# CONNECTORs.net
KiCad netlist of a schematic drawn in Altium Designer
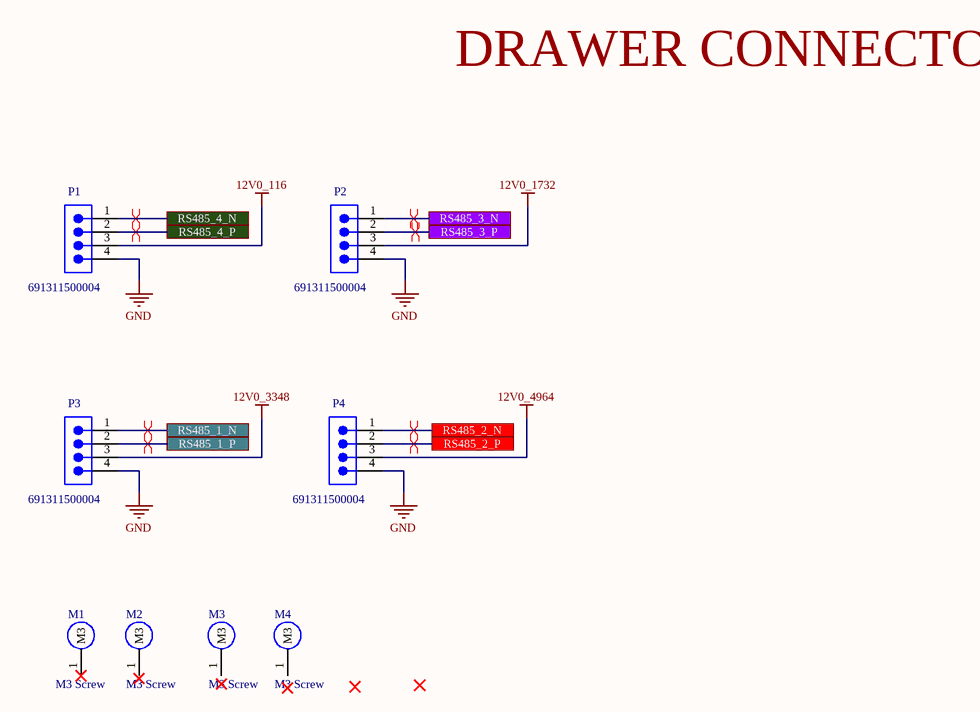
[diagram p0: CONNECTORs.SchDoc]

(export (version "E")
  (design (tool "Eeschema 10.0.6"))
  (components
    (comp (ref "M1")
      (value "M3 Screw")
      (footprint "M3_Screw")
      (description "M3 Screw Hole")
      (libsource (lib "MareLux24Lib") (part "M3 Screw"))
    )
    (comp (ref "M2")
      (value "M3 Screw")
      (footprint "M3_Screw")
      (description "M3 Screw Hole")
      (libsource (lib "MareLux24Lib") (part "M3 Screw"))
    )
    (comp (ref "M3")
      (value "M3 Screw")
      (footprint "M3_Screw")
      (description "M3 Screw Hole")
      (libsource (lib "MareLux24Lib") (part "M3 Screw"))
    )
    (comp (ref "M4")
      (value "M3 Screw")
      (footprint "M3_Screw")
      (description "M3 Screw Hole")
      (libsource (lib "MareLux24Lib") (part "M3 Screw"))
    )
    (comp (ref "P1")
      (value "691311500004")
      (footprint "691311500004")
      (description "WR-TBL Series 311 Open Vertical PCB Header, THT, pitch 5.08mm, 04p")
      (fields
        (field (name "MANUFACTURER PART NUMBER") "SBDK 5,08-E2A/4")
        (field (name "MANUFACTURER") "Wurth Elektronik")
      )
      (libsource (lib "Altium_WR-TBL_Pluggable Connector (rev25b)") (part "691311500004"))
    )
    (comp (ref "P2")
      (value "691311500004")
      (footprint "691311500004")
      (description "WR-TBL Series 311 Open Vertical PCB Header, THT, pitch 5.08mm, 04p")
      (fields
        (field (name "MANUFACTURER PART NUMBER") "SBDK 5,08-E2A/4")
        (field (name "MANUFACTURER") "Wurth Elektronik")
      )
      (libsource (lib "Altium_WR-TBL_Pluggable Connector (rev25b)") (part "691311500004"))
    )
    (comp (ref "P3")
      (value "691311500004")
      (footprint "691311500004")
      (description "WR-TBL Series 311 Open Vertical PCB Header, THT, pitch 5.08mm, 04p")
      (fields
        (field (name "MANUFACTURER PART NUMBER") "SBDK 5,08-E2A/4")
        (field (name "MANUFACTURER") "Wurth Elektronik")
      )
      (libsource (lib "Altium_WR-TBL_Pluggable Connector (rev25b)") (part "691311500004"))
    )
    (comp (ref "P4")
      (value "691311500004")
      (footprint "691311500004")
      (description "WR-TBL Series 311 Open Vertical PCB Header, THT, pitch 5.08mm, 04p")
      (fields
        (field (name "MANUFACTURER PART NUMBER") "SBDK 5,08-E2A/4")
        (field (name "MANUFACTURER") "Wurth Elektronik")
      )
      (libsource (lib "Altium_WR-TBL_Pluggable Connector (rev25b)") (part "691311500004"))
    )
  )
  (nets
    (net (code "1") (name "/RS485_1_N") (class "Default")
      (node (ref "P3") (pin "1") (pinfunction "1_1") (pintype "passive"))
    )
    (net (code "2") (name "/RS485_1_P") (class "Default")
      (node (ref "P3") (pin "2") (pinfunction "2_2") (pintype "passive"))
    )
    (net (code "3") (name "/RS485_2_N") (class "Default")
      (node (ref "P4") (pin "1") (pinfunction "1_1") (pintype "passive"))
    )
    (net (code "4") (name "/RS485_2_P") (class "Default")
      (node (ref "P4") (pin "2") (pinfunction "2_2") (pintype "passive"))
    )
    (net (code "5") (name "/RS485_3_N") (class "Default")
      (node (ref "P2") (pin "1") (pinfunction "1_1") (pintype "passive"))
    )
    (net (code "6") (name "/RS485_3_P") (class "Default")
      (node (ref "P2") (pin "2") (pinfunction "2_2") (pintype "passive"))
    )
    (net (code "7") (name "/RS485_4_N") (class "Default")
      (node (ref "P1") (pin "1") (pinfunction "1_1") (pintype "passive"))
    )
    (net (code "8") (name "/RS485_4_P") (class "Default")
      (node (ref "P1") (pin "2") (pinfunction "2_2") (pintype "passive"))
    )
    (net (code "9") (name "12V0_116") (class "Default")
      (node (ref "P1") (pin "3") (pinfunction "3_3") (pintype "passive"))
    )
    (net (code "10") (name "12V0_1732") (class "Default")
      (node (ref "P2") (pin "3") (pinfunction "3_3") (pintype "passive"))
    )
    (net (code "11") (name "12V0_3348") (class "Default")
      (node (ref "P3") (pin "3") (pinfunction "3_3") (pintype "passive"))
    )
    (net (code "12") (name "12V0_4964") (class "Default")
      (node (ref "P4") (pin "3") (pinfunction "3_3") (pintype "passive"))
    )
    (net (code "13") (name "GND") (class "Default")
      (node (ref "P1") (pin "4") (pinfunction "4_4") (pintype "passive"))
      (node (ref "P2") (pin "4") (pinfunction "4_4") (pintype "passive"))
      (node (ref "P3") (pin "4") (pinfunction "4_4") (pintype "passive"))
      (node (ref "P4") (pin "4") (pinfunction "4_4") (pintype "passive"))
    )
    (net (code "14") (name "unconnected-(M1-M3-Pad1)") (class "Default")
      (node (ref "M1") (pin "1") (pinfunction "M3_1") (pintype "passive+no_connect"))
    )
    (net (code "15") (name "unconnected-(M2-M3-Pad1)") (class "Default")
      (node (ref "M2") (pin "1") (pinfunction "M3_1") (pintype "passive"))
    )
    (net (code "16") (name "unconnected-(M3-M3-Pad1)") (class "Default")
      (node (ref "M3") (pin "1") (pinfunction "M3_1") (pintype "passive"))
    )
    (net (code "17") (name "unconnected-(M4-M3-Pad1)") (class "Default")
      (node (ref "M4") (pin "1") (pinfunction "M3_1") (pintype "passive"))
    )
  )
)
